# MotorControl.net
KiCad netlist of a schematic drawn in Altium Designer
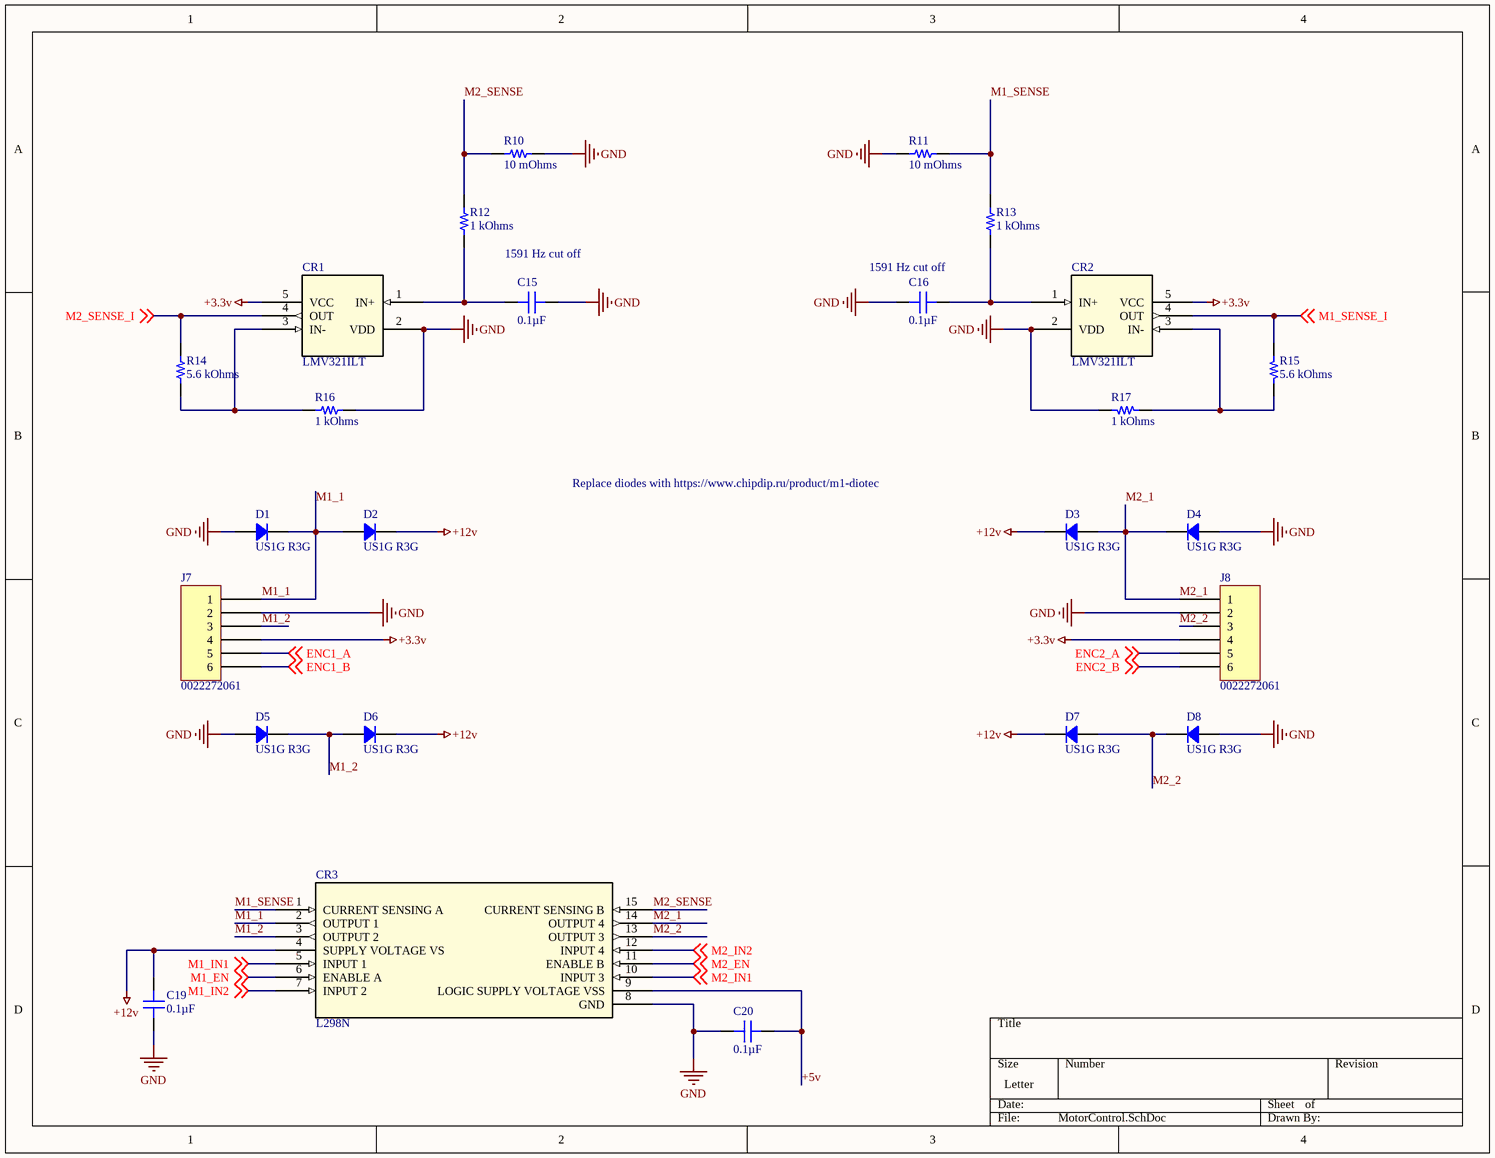
[diagram p0: MotorControl.SchDoc]

(export (version "E")
  (design (tool "Eeschema 10.0.6"))
  (components
    (comp (ref "C15")
      (value "0.1µF")
      (footprint "CAP 0805_2012")
      (description "CAP CER 0.1UF 16V Y5V 0805")
      (fields
        (field (name "PART NUMBER") "VJ0805V104ZXJCW1BC")
        (field (name "MANUFACTURER") "Vishay Vitramon")
      )
      (libsource (lib "Celestial Altium Library - altium_library") (part "Capacitor"))
    )
    (comp (ref "C16")
      (value "0.1µF")
      (footprint "CAP 0805_2012")
      (description "CAP CER 0.1UF 16V Y5V 0805")
      (fields
        (field (name "PART NUMBER") "VJ0805V104ZXJCW1BC")
        (field (name "MANUFACTURER") "Vishay Vitramon")
      )
      (libsource (lib "Celestial Altium Library - altium_library") (part "Capacitor"))
    )
    (comp (ref "C19")
      (value "0.1µF")
      (footprint "CAP 0805_2012")
      (description "CAP CER 0.1UF 50V X7R 0805")
      (fields (field (name "PART NUMBER") "CC0805MRX7R9BB104") (field (name "MANUFACTURER") "Yageo"))
      (libsource (lib "Celestial Altium Library - altium_library") (part "Capacitor"))
    )
    (comp (ref "C20")
      (value "0.1µF")
      (footprint "CAP 0805_2012")
      (description "CAP CER 0.1UF 50V X7R 0805")
      (fields (field (name "PART NUMBER") "CC0805MRX7R9BB104") (field (name "MANUFACTURER") "Yageo"))
      (libsource (lib "Celestial Altium Library - altium_library") (part "Capacitor"))
    )
    (comp (ref "CR1")
      (value "LMV321ILT")
      (footprint "SOT23-5_STM")
      (description "No Description Available")
      (fields (field (name "COPYRIGHT") "Copyright (C) 2018 Accelerated Designs. All rights reserved"))
      (libsource (lib "") (part "LMV321ILT_1"))
    )
    (comp (ref "CR2")
      (value "LMV321ILT")
      (footprint "SOT23-5_STM")
      (description "No Description Available")
      (fields (field (name "COPYRIGHT") "Copyright (C) 2018 Accelerated Designs. All rights reserved"))
      (libsource (lib "LMV321ILT") (part "LMV321ILT"))
    )
    (comp (ref "CR3")
      (value "L298N")
      (footprint "Multiwatt15_V_STM")
      (description "No Description Available")
      (fields (field (name "COPYRIGHT") "Copyright (C) 2018 Accelerated Designs. All rights reserved"))
      (libsource (lib "L298N") (part "L298N"))
    )
    (comp (ref "D1")
      (value "US1G R3G")
      (footprint "DO214AC SMA")
      (description "DIODE GEN PURP 400V 1A DO214AC")
      (fields (field (name "MANUFACTURER") "Taiwan Semiconductor Corporation"))
      (libsource (lib "Celestial Altium Library - altium_library") (part "Diode"))
    )
    (comp (ref "D2")
      (value "US1G R3G")
      (footprint "DO214AC SMA")
      (description "DIODE GEN PURP 400V 1A DO214AC")
      (fields (field (name "MANUFACTURER") "Taiwan Semiconductor Corporation"))
      (libsource (lib "Celestial Altium Library - altium_library") (part "Diode"))
    )
    (comp (ref "D3")
      (value "US1G R3G")
      (footprint "DO214AC SMA")
      (description "DIODE GEN PURP 400V 1A DO214AC")
      (fields (field (name "MANUFACTURER") "Taiwan Semiconductor Corporation"))
      (libsource (lib "Celestial Altium Library - altium_library") (part "Diode"))
    )
    (comp (ref "D4")
      (value "US1G R3G")
      (footprint "DO214AC SMA")
      (description "DIODE GEN PURP 400V 1A DO214AC")
      (fields (field (name "MANUFACTURER") "Taiwan Semiconductor Corporation"))
      (libsource (lib "Celestial Altium Library - altium_library") (part "Diode"))
    )
    (comp (ref "D5")
      (value "US1G R3G")
      (footprint "DO214AC SMA")
      (description "DIODE GEN PURP 400V 1A DO214AC")
      (fields (field (name "MANUFACTURER") "Taiwan Semiconductor Corporation"))
      (libsource (lib "Celestial Altium Library - altium_library") (part "Diode"))
    )
    (comp (ref "D6")
      (value "US1G R3G")
      (footprint "DO214AC SMA")
      (description "DIODE GEN PURP 400V 1A DO214AC")
      (fields (field (name "MANUFACTURER") "Taiwan Semiconductor Corporation"))
      (libsource (lib "Celestial Altium Library - altium_library") (part "Diode"))
    )
    (comp (ref "D7")
      (value "US1G R3G")
      (footprint "DO214AC SMA")
      (description "DIODE GEN PURP 400V 1A DO214AC")
      (fields (field (name "MANUFACTURER") "Taiwan Semiconductor Corporation"))
      (libsource (lib "Celestial Altium Library - altium_library") (part "Diode"))
    )
    (comp (ref "D8")
      (value "US1G R3G")
      (footprint "DO214AC SMA")
      (description "DIODE GEN PURP 400V 1A DO214AC")
      (fields (field (name "MANUFACTURER") "Taiwan Semiconductor Corporation"))
      (libsource (lib "Celestial Altium Library - altium_library") (part "Diode"))
    )
    (comp (ref "J7")
      (value "0022272061")
      (footprint "MOLEX KK 0022272061")
      (description "CONN HEADER VERT 6POS 2.54MM")
      (fields (field (name "MANUFACTURER") "Molex"))
      (libsource (lib "Celestial Altium Library - altium_library") (part "6 Pin"))
    )
    (comp (ref "J8")
      (value "0022272061")
      (footprint "MOLEX KK 0022272061")
      (description "CONN HEADER VERT 6POS 2.54MM")
      (fields (field (name "MANUFACTURER") "Molex"))
      (libsource (lib "") (part "6 Pin_1"))
    )
    (comp (ref "R10")
      (value "10 mOhms")
      (footprint "RES 1206_3216")
      (description "RES 0.01 OHM 1% 1W 1206")
      (fields (field (name "PART NUMBER") "LVT12R0100FER") (field (name "MANUFACTURER") "Ohmite"))
      (libsource (lib "Celestial Altium Library - altium_library") (part "Resistor"))
    )
    (comp (ref "R11")
      (value "10 mOhms")
      (footprint "RES 1206_3216")
      (description "RES 0.01 OHM 1% 1W 1206")
      (fields (field (name "PART NUMBER") "LVT12R0100FER") (field (name "MANUFACTURER") "Ohmite"))
      (libsource (lib "Celestial Altium Library - altium_library") (part "Resistor"))
    )
    (comp (ref "R12")
      (value "1 kOhms")
      (footprint "RES 0805_2012")
      (description "RES 1K OHM 1% 1/8W 0805")
      (fields
        (field (name "PART NUMBER") "RN73R2ATTD1001F50")
        (field (name "MANUFACTURER") "KOA Speer Electronics, Inc.")
      )
      (libsource (lib "Celestial Altium Library - altium_library") (part "Resistor"))
    )
    (comp (ref "R13")
      (value "1 kOhms")
      (footprint "RES 0805_2012")
      (description "RES 1K OHM 1% 1/8W 0805")
      (fields
        (field (name "PART NUMBER") "RN73R2ATTD1001F50")
        (field (name "MANUFACTURER") "KOA Speer Electronics, Inc.")
      )
      (libsource (lib "Celestial Altium Library - altium_library") (part "Resistor"))
    )
    (comp (ref "R14")
      (value "5.6 kOhms")
      (footprint "RES 0805_2012")
      (description "RES SMD 5.6K OHM 1% 1/8W 0805")
      (fields
        (field (name "PART NUMBER") "ERJ-6ENF5601V")
        (field (name "MANUFACTURER") "Panasonic Electronic Components")
      )
      (libsource (lib "Celestial Altium Library - altium_library") (part "Resistor"))
    )
    (comp (ref "R15")
      (value "5.6 kOhms")
      (footprint "RES 0805_2012")
      (description "RES SMD 5.6K OHM 1% 1/8W 0805")
      (fields
        (field (name "PART NUMBER") "ERJ-6ENF5601V")
        (field (name "MANUFACTURER") "Panasonic Electronic Components")
      )
      (libsource (lib "Celestial Altium Library - altium_library") (part "Resistor"))
    )
    (comp (ref "R16")
      (value "1 kOhms")
      (footprint "RES 0805_2012")
      (description "RES SMD 1K OHM 1% 1/8W 0805")
      (fields (field (name "PART NUMBER") "CRCW08051K00FKEA") (field (name "MANUFACTURER") "Vishay Dale"))
      (libsource (lib "Celestial Altium Library - altium_library") (part "Resistor"))
    )
    (comp (ref "R17")
      (value "1 kOhms")
      (footprint "RES 0805_2012")
      (description "RES SMD 1K OHM 1% 1/8W 0805")
      (fields (field (name "PART NUMBER") "CRCW08051K00FKEA") (field (name "MANUFACTURER") "Vishay Dale"))
      (libsource (lib "Celestial Altium Library - altium_library") (part "Resistor"))
    )
  )
  (nets
    (net (code "1") (name "+3.3v") (class "Default")
      (node (ref "CR1") (pin "5") (pinfunction "VCC_5") (pintype "power_in"))
      (node (ref "CR2") (pin "5") (pinfunction "VCC_5") (pintype "power_in"))
      (node (ref "J7") (pin "4") (pinfunction "4_4") (pintype "passive"))
      (node (ref "J8") (pin "4") (pinfunction "4_4") (pintype "passive"))
    )
    (net (code "2") (name "+12v") (class "Default")
      (node (ref "C19") (pin "2") (pinfunction "2_2") (pintype "passive"))
      (node (ref "CR3") (pin "4") (pinfunction "SUPPLY_VOLTAGE_VS_4") (pintype "power_in"))
      (node (ref "D2") (pin "2") (pinfunction "2_2") (pintype "passive"))
      (node (ref "D3") (pin "2") (pinfunction "2_2") (pintype "passive"))
      (node (ref "D6") (pin "2") (pinfunction "2_2") (pintype "passive"))
      (node (ref "D7") (pin "2") (pinfunction "2_2") (pintype "passive"))
    )
    (net (code "3") (name "/+5v") (class "Default")
      (node (ref "C20") (pin "2") (pinfunction "2_2") (pintype "passive"))
      (node (ref "CR3") (pin "9") (pinfunction "LOGIC_SUPPLY_VOLTAGE_VSS_9") (pintype "power_in"))
    )
    (net (code "4") (name "/M1_1") (class "Default")
      (node (ref "CR3") (pin "2") (pinfunction "OUTPUT_1_2") (pintype "output"))
      (node (ref "D1") (pin "2") (pinfunction "2_2") (pintype "passive"))
      (node (ref "D2") (pin "1") (pinfunction "1_1") (pintype "passive"))
      (node (ref "J7") (pin "1") (pinfunction "1_1") (pintype "passive"))
    )
    (net (code "5") (name "/M1_2") (class "Default")
      (node (ref "CR3") (pin "3") (pinfunction "OUTPUT_2_3") (pintype "output"))
      (node (ref "D5") (pin "2") (pinfunction "2_2") (pintype "passive"))
      (node (ref "D6") (pin "1") (pinfunction "1_1") (pintype "passive"))
      (node (ref "J7") (pin "3") (pinfunction "3_3") (pintype "passive"))
    )
    (net (code "6") (name "/M1_SENSE") (class "Default")
      (node (ref "CR3") (pin "1") (pinfunction "CURRENT_SENSING_A_1") (pintype "input"))
      (node (ref "R11") (pin "2") (pinfunction "2_2") (pintype "passive"))
      (node (ref "R13") (pin "2") (pinfunction "2_2") (pintype "passive"))
    )
    (net (code "7") (name "/M2_1") (class "Default")
      (node (ref "CR3") (pin "14") (pinfunction "OUTPUT_4_14") (pintype "output"))
      (node (ref "D3") (pin "1") (pinfunction "1_1") (pintype "passive"))
      (node (ref "D4") (pin "2") (pinfunction "2_2") (pintype "passive"))
      (node (ref "J8") (pin "1") (pinfunction "1_1") (pintype "passive"))
    )
    (net (code "8") (name "/M2_2") (class "Default")
      (node (ref "CR3") (pin "13") (pinfunction "OUTPUT_3_13") (pintype "output"))
      (node (ref "D7") (pin "1") (pinfunction "1_1") (pintype "passive"))
      (node (ref "D8") (pin "2") (pinfunction "2_2") (pintype "passive"))
      (node (ref "J8") (pin "3") (pinfunction "3_3") (pintype "passive"))
    )
    (net (code "9") (name "/M2_SENSE") (class "Default")
      (node (ref "CR3") (pin "15") (pinfunction "CURRENT_SENSING_B_15") (pintype "input"))
      (node (ref "R10") (pin "1") (pinfunction "1_1") (pintype "passive"))
      (node (ref "R12") (pin "2") (pinfunction "2_2") (pintype "passive"))
    )
    (net (code "10") (name "ENC1_A") (class "Default")
      (node (ref "J7") (pin "5") (pinfunction "5_5") (pintype "passive"))
    )
    (net (code "11") (name "ENC1_B") (class "Default")
      (node (ref "J7") (pin "6") (pinfunction "6_6") (pintype "passive"))
    )
    (net (code "12") (name "ENC2_A") (class "Default")
      (node (ref "J8") (pin "5") (pinfunction "5_5") (pintype "passive"))
    )
    (net (code "13") (name "ENC2_B") (class "Default")
      (node (ref "J8") (pin "6") (pinfunction "6_6") (pintype "passive"))
    )
    (net (code "14") (name "GND") (class "Default")
      (node (ref "C15") (pin "2") (pinfunction "2_2") (pintype "passive"))
      (node (ref "C16") (pin "1") (pinfunction "1_1") (pintype "passive"))
      (node (ref "C19") (pin "1") (pinfunction "1_1") (pintype "passive"))
      (node (ref "C20") (pin "1") (pinfunction "1_1") (pintype "passive"))
      (node (ref "CR1") (pin "2") (pinfunction "VDD_2") (pintype "power_in"))
      (node (ref "CR2") (pin "2") (pinfunction "VDD_2") (pintype "power_in"))
      (node (ref "CR3") (pin "8") (pinfunction "GND_8") (pintype "passive"))
      (node (ref "D1") (pin "1") (pinfunction "1_1") (pintype "passive"))
      (node (ref "D4") (pin "1") (pinfunction "1_1") (pintype "passive"))
      (node (ref "D5") (pin "1") (pinfunction "1_1") (pintype "passive"))
      (node (ref "D8") (pin "1") (pinfunction "1_1") (pintype "passive"))
      (node (ref "J7") (pin "2") (pinfunction "2_2") (pintype "passive"))
      (node (ref "J8") (pin "2") (pinfunction "2_2") (pintype "passive"))
      (node (ref "R10") (pin "2") (pinfunction "2_2") (pintype "passive"))
      (node (ref "R11") (pin "1") (pinfunction "1_1") (pintype "passive"))
      (node (ref "R16") (pin "2") (pinfunction "2_2") (pintype "passive"))
      (node (ref "R17") (pin "2") (pinfunction "2_2") (pintype "passive"))
    )
    (net (code "15") (name "M1_EN") (class "Default")
      (node (ref "CR3") (pin "6") (pinfunction "ENABLE_A_6") (pintype "input"))
    )
    (net (code "16") (name "M1_IN1") (class "Default")
      (node (ref "CR3") (pin "5") (pinfunction "INPUT_1_5") (pintype "input"))
    )
    (net (code "17") (name "M1_IN2") (class "Default")
      (node (ref "CR3") (pin "7") (pinfunction "INPUT_2_7") (pintype "input"))
    )
    (net (code "18") (name "M1_SENSE_I") (class "Default")
      (node (ref "CR2") (pin "4") (pinfunction "OUT_4") (pintype "output"))
      (node (ref "R15") (pin "2") (pinfunction "2_2") (pintype "passive"))
    )
    (net (code "19") (name "M2_EN") (class "Default")
      (node (ref "CR3") (pin "11") (pinfunction "ENABLE_B_11") (pintype "input"))
    )
    (net (code "20") (name "M2_IN1") (class "Default")
      (node (ref "CR3") (pin "10") (pinfunction "INPUT_3_10") (pintype "input"))
    )
    (net (code "21") (name "M2_IN2") (class "Default")
      (node (ref "CR3") (pin "12") (pinfunction "INPUT_4_12") (pintype "input"))
    )
    (net (code "22") (name "M2_SENSE_I") (class "Default")
      (node (ref "CR1") (pin "4") (pinfunction "OUT_4") (pintype "output"))
      (node (ref "R14") (pin "2") (pinfunction "2_2") (pintype "passive"))
    )
    (net (code "23") (name "Net-(CR1-IN+)") (class "Default")
      (node (ref "C15") (pin "1") (pinfunction "1_1") (pintype "passive"))
      (node (ref "CR1") (pin "1") (pinfunction "IN+_1") (pintype "input"))
      (node (ref "R12") (pin "1") (pinfunction "1_1") (pintype "passive"))
    )
    (net (code "24") (name "Net-(CR1-IN-)") (class "Default")
      (node (ref "CR1") (pin "3") (pinfunction "IN-_3") (pintype "input"))
      (node (ref "R14") (pin "1") (pinfunction "1_1") (pintype "passive"))
      (node (ref "R16") (pin "1") (pinfunction "1_1") (pintype "passive"))
    )
    (net (code "25") (name "Net-(CR2-IN+)") (class "Default")
      (node (ref "C16") (pin "2") (pinfunction "2_2") (pintype "passive"))
      (node (ref "CR2") (pin "1") (pinfunction "IN+_1") (pintype "input"))
      (node (ref "R13") (pin "1") (pinfunction "1_1") (pintype "passive"))
    )
    (net (code "26") (name "Net-(CR2-IN-)") (class "Default")
      (node (ref "CR2") (pin "3") (pinfunction "IN-_3") (pintype "input"))
      (node (ref "R15") (pin "1") (pinfunction "1_1") (pintype "passive"))
      (node (ref "R17") (pin "1") (pinfunction "1_1") (pintype "passive"))
    )
  )
)
